# NullAnalyser.net
KiCad netlist of a schematic drawn in EAGLE
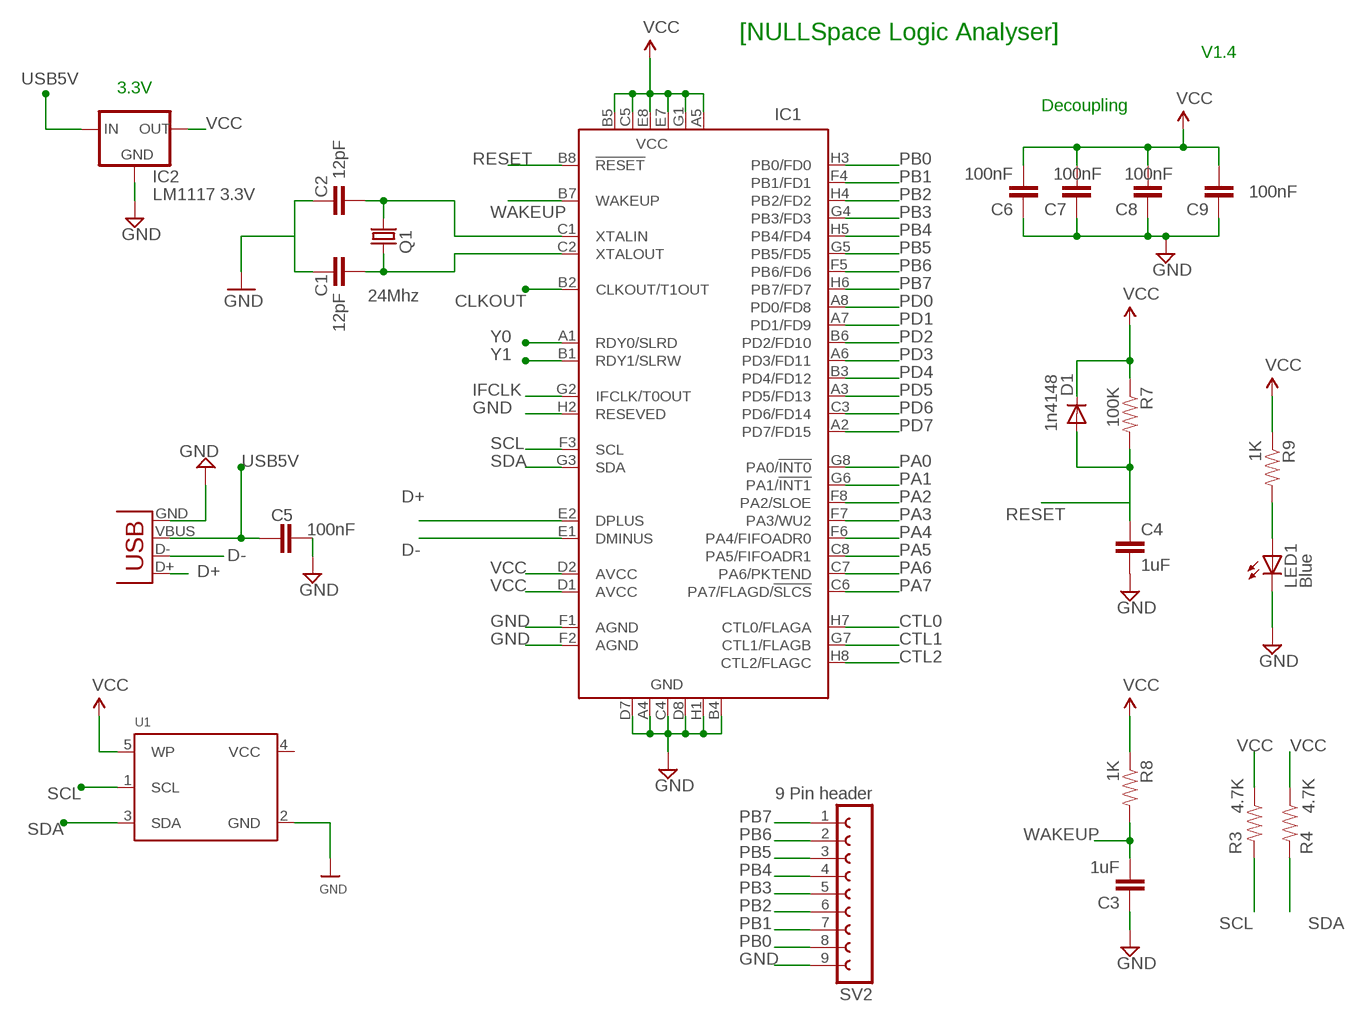
[diagram p0: schematic, sheet 1]

(export (version "E")
  (design (tool "Eeschema 10.0.6"))
  (components
    (comp (ref "C1")
      (value "12pF")
      (footprint "eagle-import:0402-CAP")
      (fields (field (name "MF") "KEMET") (field (name "MPN") "C0805C120J5GACTU"))
      (libsource (lib "eagle-import") (part "CAP0402-CAP"))
    )
    (comp (ref "C2")
      (value "12pF")
      (footprint "eagle-import:0402-CAP")
      (fields (field (name "MF") "KEMET") (field (name "MPN") "C0805C120J5GACTU"))
      (libsource (lib "eagle-import") (part "CAP0402-CAP"))
    )
    (comp (ref "C3")
      (value "1uF")
      (footprint "eagle-import:0402-CAP")
      (fields (field (name "MPN") "C2012Y5V1C105Z/0.85"))
      (libsource (lib "eagle-import") (part "CAP0402-CAP"))
    )
    (comp (ref "C4")
      (value "1uF")
      (footprint "eagle-import:0402-CAP")
      (fields (field (name "MPN") "C2012Y5V1C105Z/0.85"))
      (libsource (lib "eagle-import") (part "CAP0402-CAP"))
    )
    (comp (ref "C5")
      (value "100nF")
      (footprint "eagle-import:0402-CAP")
      (fields (field (name "MF") "FARNELL") (field (name "MPN") "GRM21BR71H104KA01L"))
      (libsource (lib "eagle-import") (part "CAP0402-CAP"))
    )
    (comp (ref "C6")
      (value "100nF")
      (footprint "eagle-import:0402-CAP")
      (fields (field (name "MF") "FARNELL") (field (name "MPN") "GRM21BR71H104KA01L"))
      (libsource (lib "eagle-import") (part "CAP0402-CAP"))
    )
    (comp (ref "C7")
      (value "100nF")
      (footprint "eagle-import:0402-CAP")
      (fields (field (name "MF") "FARNELL") (field (name "MPN") "GRM21BR71H104KA01L"))
      (libsource (lib "eagle-import") (part "CAP0402-CAP"))
    )
    (comp (ref "C8")
      (value "100nF")
      (footprint "eagle-import:0402-CAP")
      (fields (field (name "MF") "FARNELL") (field (name "MPN") "GRM21BR71H104KA01L"))
      (libsource (lib "eagle-import") (part "CAP0402-CAP"))
    )
    (comp (ref "C9")
      (value "100nF")
      (footprint "eagle-import:0402-CAP")
      (fields (field (name "MF") "FARNELL") (field (name "MPN") "GRM21BR71H104KA01L"))
      (libsource (lib "eagle-import") (part "CAP0402-CAP"))
    )
    (comp (ref "D1")
      (value "1n4148")
      (footprint "eagle-import:SOD-323")
      (fields (field (name "MF") "VISHAY/TELEFUNKEN") (field (name "MPN") "1N4148W-V-GS08"))
      (libsource (lib "eagle-import") (part "DIODESOD"))
    )
    (comp (ref "IC1")
      (value "CY7C68014A-56BAXC")
      (footprint "eagle-import:VFBGA56")
      (fields (field (name "MPN") "CY7C68014A-56BAXC") (field (name "OC_NEWARK") "23M5564"))
      (libsource (lib "eagle-import") (part "CY7C6801A-56BAXC4"))
    )
    (comp (ref "IC2")
      (value "LM1117 3.3V")
      (footprint "eagle-import:SOT223")
      (fields (field (name "MF") "NATIONAL SEMICONDUCTOR") (field (name "MPN") "LM1117MPX-3.3"))
      (libsource (lib "eagle-import") (part "LM1117"))
    )
    (comp (ref "LED1")
      (value "Blue")
      (footprint "eagle-import:LED-0603")
      (fields (field (name "MPN") "5988210107F"))
      (libsource (lib "eagle-import") (part "LED0603"))
    )
    (comp (ref "Q1")
      (value "24Mhz")
      (footprint "eagle-import:CRYSTAL-SMD-TWO-PAD")
      (fields (field (name "MF") "Abracon Corporation") (field (name "MPN") "ABM3-24.000MHZ-B2-T"))
      (libsource (lib "eagle-import") (part "CRYSTALTWO-PADTWO-PAD"))
    )
    (comp (ref "R3")
      (value "4.7K")
      (footprint "eagle-import:0402-RES")
      (fields (field (name "MPN") "CRCW08054K70JNEA"))
      (libsource (lib "eagle-import") (part "RESISTOR0402-RES"))
    )
    (comp (ref "R4")
      (value "4.7K")
      (footprint "eagle-import:0402-RES")
      (fields (field (name "MPN") "CRCW08054K70JNEA"))
      (libsource (lib "eagle-import") (part "RESISTOR0402-RES"))
    )
    (comp (ref "R7")
      (value "100K")
      (footprint "eagle-import:0402-RES")
      (fields (field (name "MPN") "MCTF0805DTC1002"))
      (libsource (lib "eagle-import") (part "RESISTOR0402-RES"))
    )
    (comp (ref "R8")
      (value "1K")
      (footprint "eagle-import:0402-RES")
      (fields (field (name "MPN") "MCTF0805DTC1001"))
      (libsource (lib "eagle-import") (part "RESISTOR0402-RES"))
    )
    (comp (ref "R9")
      (value "1K")
      (footprint "eagle-import:0402-RES")
      (fields (field (name "MPN") "MCTF0805DTC1001"))
      (libsource (lib "eagle-import") (part "RESISTOR0402-RES"))
    )
    (comp (ref "SV2")
      (value "9 Pin header")
      (footprint "eagle-import:FE09")
      (fields (field (name "OC_NEWARK") "unknown"))
      (libsource (lib "eagle-import") (part "FE09-1"))
    )
    (comp (ref "U1")
      (value "MCP24AA32")
      (footprint "eagle-import:SOT23-5")
      (fields (field (name "MF") "MICROCHIP") (field (name "MPN") "24LC00T-I/OT"))
      (libsource (lib "eagle-import") (part "MCP24AA32"))
    )
    (comp (ref "X1")
      (value "USB-MICROB")
      (footprint "eagle-import:USB-MICROB")
      (fields (field (name "MPN") "1734035-1"))
      (libsource (lib "eagle-import") (part "USB-MICROB"))
    )
  )
  (nets
    (net (code "1") (name "/CLKOUT") (class "Default")
      (node (ref "IC1") (pin "B2") (pinfunction "CLKOUT/T1OUT_B2") (pintype "input"))
    )
    (net (code "2") (name "/CTL0") (class "Default")
      (node (ref "IC1") (pin "H7") (pinfunction "CTL0/FLAGA_H7") (pintype "output"))
    )
    (net (code "3") (name "/CTL1") (class "Default")
      (node (ref "IC1") (pin "G7") (pinfunction "CTL1/FLAGB_G7") (pintype "output"))
    )
    (net (code "4") (name "/CTL2") (class "Default")
      (node (ref "IC1") (pin "H8") (pinfunction "CTL2/FLAGC_H8") (pintype "output"))
    )
    (net (code "5") (name "/D+") (class "Default")
      (node (ref "IC1") (pin "E2") (pinfunction "DPLUS_E2") (pintype "bidirectional"))
      (node (ref "X1") (pin "D+") (pinfunction "D+_D+") (pintype "bidirectional"))
    )
    (net (code "6") (name "/D-") (class "Default")
      (node (ref "IC1") (pin "E1") (pinfunction "DMINUS_E1") (pintype "bidirectional"))
      (node (ref "X1") (pin "D-") (pinfunction "D-_D-") (pintype "bidirectional"))
    )
    (net (code "7") (name "/IFCLK") (class "Default")
      (node (ref "IC1") (pin "G2") (pinfunction "IFCLK/T0OUT_G2") (pintype "bidirectional"))
    )
    (net (code "8") (name "/PA0") (class "Default")
      (node (ref "IC1") (pin "G8") (pinfunction "PA0/~{INT0}_G8") (pintype "bidirectional"))
    )
    (net (code "9") (name "/PA1") (class "Default")
      (node (ref "IC1") (pin "G6") (pinfunction "PA1/~{INT1}_G6") (pintype "bidirectional"))
    )
    (net (code "10") (name "/PA2") (class "Default")
      (node (ref "IC1") (pin "F8") (pinfunction "PA2/SLOE_F8") (pintype "bidirectional"))
    )
    (net (code "11") (name "/PA3") (class "Default")
      (node (ref "IC1") (pin "F7") (pinfunction "PA3/WU2_F7") (pintype "bidirectional"))
    )
    (net (code "12") (name "/PA4") (class "Default")
      (node (ref "IC1") (pin "F6") (pinfunction "PA4/FIFOADR0_F6") (pintype "bidirectional"))
    )
    (net (code "13") (name "/PA5") (class "Default")
      (node (ref "IC1") (pin "C8") (pinfunction "PA5/FIFOADR1_C8") (pintype "bidirectional"))
    )
    (net (code "14") (name "/PA6") (class "Default")
      (node (ref "IC1") (pin "C7") (pinfunction "PA6/PKTEND_C7") (pintype "bidirectional"))
    )
    (net (code "15") (name "/PA7") (class "Default")
      (node (ref "IC1") (pin "C6") (pinfunction "PA7/FLAGD/~{SLCS}_C6") (pintype "bidirectional"))
    )
    (net (code "16") (name "/PB0") (class "Default")
      (node (ref "IC1") (pin "H3") (pinfunction "PB0/FD0_H3") (pintype "bidirectional"))
      (node (ref "SV2") (pin "8") (pinfunction "8_8") (pintype "passive"))
    )
    (net (code "17") (name "/PB1") (class "Default")
      (node (ref "IC1") (pin "F4") (pinfunction "PB1/FD1_F4") (pintype "bidirectional"))
      (node (ref "SV2") (pin "7") (pinfunction "7_7") (pintype "passive"))
    )
    (net (code "18") (name "/PB2") (class "Default")
      (node (ref "IC1") (pin "H4") (pinfunction "PB2/FD2_H4") (pintype "bidirectional"))
      (node (ref "SV2") (pin "6") (pinfunction "6_6") (pintype "passive"))
    )
    (net (code "19") (name "/PB3") (class "Default")
      (node (ref "IC1") (pin "G4") (pinfunction "PB3/FD3_G4") (pintype "bidirectional"))
      (node (ref "SV2") (pin "5") (pinfunction "5_5") (pintype "passive"))
    )
    (net (code "20") (name "/PB4") (class "Default")
      (node (ref "IC1") (pin "H5") (pinfunction "PB4/FD4_H5") (pintype "bidirectional"))
      (node (ref "SV2") (pin "4") (pinfunction "4_4") (pintype "passive"))
    )
    (net (code "21") (name "/PB5") (class "Default")
      (node (ref "IC1") (pin "G5") (pinfunction "PB5/FD5_G5") (pintype "bidirectional"))
      (node (ref "SV2") (pin "3") (pinfunction "3_3") (pintype "passive"))
    )
    (net (code "22") (name "/PB6") (class "Default")
      (node (ref "IC1") (pin "F5") (pinfunction "PB6/FD6_F5") (pintype "bidirectional"))
      (node (ref "SV2") (pin "2") (pinfunction "2_2") (pintype "passive"))
    )
    (net (code "23") (name "/PB7") (class "Default")
      (node (ref "IC1") (pin "H6") (pinfunction "PB7/FD7_H6") (pintype "bidirectional"))
      (node (ref "SV2") (pin "1") (pinfunction "1_1") (pintype "passive"))
    )
    (net (code "24") (name "/PD0") (class "Default")
      (node (ref "IC1") (pin "A8") (pinfunction "PD0/FD8_A8") (pintype "bidirectional"))
    )
    (net (code "25") (name "/PD1") (class "Default")
      (node (ref "IC1") (pin "A7") (pinfunction "PD1/FD9_A7") (pintype "bidirectional"))
    )
    (net (code "26") (name "/PD2") (class "Default")
      (node (ref "IC1") (pin "B6") (pinfunction "PD2/FD10_B6") (pintype "bidirectional"))
    )
    (net (code "27") (name "/PD3") (class "Default")
      (node (ref "IC1") (pin "A6") (pinfunction "PD3/FD11_A6") (pintype "bidirectional"))
    )
    (net (code "28") (name "/PD4") (class "Default")
      (node (ref "IC1") (pin "B3") (pinfunction "PD4/FD12_B3") (pintype "bidirectional"))
    )
    (net (code "29") (name "/PD5") (class "Default")
      (node (ref "IC1") (pin "A3") (pinfunction "PD5/FD13_A3") (pintype "bidirectional"))
    )
    (net (code "30") (name "/PD6") (class "Default")
      (node (ref "IC1") (pin "C3") (pinfunction "PD6/FD14_C3") (pintype "bidirectional"))
    )
    (net (code "31") (name "/PD7") (class "Default")
      (node (ref "IC1") (pin "A2") (pinfunction "PD7/FD15_A2") (pintype "bidirectional"))
    )
    (net (code "32") (name "/RESET") (class "Default")
      (node (ref "C4") (pin "1") (pinfunction "1_1") (pintype "passive"))
      (node (ref "D1") (pin "2") (pinfunction "A_2") (pintype "passive"))
      (node (ref "IC1") (pin "B8") (pinfunction "~{RESET}_B8") (pintype "input"))
      (node (ref "R7") (pin "2") (pinfunction "2_2") (pintype "passive"))
    )
    (net (code "33") (name "/SCL") (class "Default")
      (node (ref "IC1") (pin "F3") (pinfunction "SCL_F3") (pintype "output"))
      (node (ref "R3") (pin "2") (pinfunction "2_2") (pintype "passive"))
      (node (ref "U1") (pin "1") (pinfunction "SCL_1") (pintype "bidirectional"))
    )
    (net (code "34") (name "/SDA") (class "Default")
      (node (ref "IC1") (pin "G3") (pinfunction "SDA_G3") (pintype "bidirectional"))
      (node (ref "R4") (pin "2") (pinfunction "2_2") (pintype "passive"))
      (node (ref "U1") (pin "3") (pinfunction "SDA_3") (pintype "bidirectional"))
    )
    (net (code "35") (name "/USB5V") (class "Default")
      (node (ref "C5") (pin "1") (pinfunction "1_1") (pintype "passive"))
      (node (ref "IC2") (pin "3") (pinfunction "IN_3") (pintype "input"))
      (node (ref "X1") (pin "VBUS") (pinfunction "VBUS_VBUS") (pintype "bidirectional"))
    )
    (net (code "36") (name "/WAKEUP") (class "Default")
      (node (ref "C3") (pin "2") (pinfunction "2_2") (pintype "passive"))
      (node (ref "IC1") (pin "B7") (pinfunction "WAKEUP_B7") (pintype "input"))
      (node (ref "R8") (pin "2") (pinfunction "2_2") (pintype "passive"))
    )
    (net (code "37") (name "/Y0") (class "Default")
      (node (ref "IC1") (pin "A1") (pinfunction "RDY0/SLRD_A1") (pintype "input"))
    )
    (net (code "38") (name "/Y1") (class "Default")
      (node (ref "IC1") (pin "B1") (pinfunction "RDY1/SLRW_B1") (pintype "input"))
    )
    (net (code "39") (name "GND") (class "Default")
      (node (ref "C1") (pin "1") (pinfunction "1_1") (pintype "passive"))
      (node (ref "C2") (pin "2") (pinfunction "2_2") (pintype "passive"))
      (node (ref "C3") (pin "1") (pinfunction "1_1") (pintype "passive"))
      (node (ref "C4") (pin "2") (pinfunction "2_2") (pintype "passive"))
      (node (ref "C5") (pin "2") (pinfunction "2_2") (pintype "passive"))
      (node (ref "C6") (pin "1") (pinfunction "1_1") (pintype "passive"))
      (node (ref "C7") (pin "1") (pinfunction "1_1") (pintype "passive"))
      (node (ref "C8") (pin "1") (pinfunction "1_1") (pintype "passive"))
      (node (ref "C9") (pin "1") (pinfunction "1_1") (pintype "passive"))
      (node (ref "IC1") (pin "A4") (pinfunction "GND_A4") (pintype "input"))
      (node (ref "IC1") (pin "B4") (pinfunction "GND_B4") (pintype "input"))
      (node (ref "IC1") (pin "C4") (pinfunction "GND_C4") (pintype "input"))
      (node (ref "IC1") (pin "D7") (pinfunction "GND_D7") (pintype "input"))
      (node (ref "IC1") (pin "D8") (pinfunction "GND_D8") (pintype "input"))
      (node (ref "IC1") (pin "F1") (pinfunction "AGND_F1") (pintype "input"))
      (node (ref "IC1") (pin "F2") (pinfunction "AGND_F2") (pintype "input"))
      (node (ref "IC1") (pin "H1") (pinfunction "GND_H1") (pintype "input"))
      (node (ref "IC1") (pin "H2") (pinfunction "RESEVED_H2") (pintype "input"))
      (node (ref "IC2") (pin "1") (pinfunction "GND_1") (pintype "input"))
      (node (ref "LED1") (pin "C") (pinfunction "C_C") (pintype "passive"))
      (node (ref "SV2") (pin "9") (pinfunction "9_9") (pintype "passive"))
      (node (ref "U1") (pin "2") (pinfunction "GND_2") (pintype "bidirectional"))
      (node (ref "X1") (pin "GND") (pinfunction "GND_GND") (pintype "bidirectional"))
    )
    (net (code "40") (name "Net-(IC1-XTALIN)") (class "Default")
      (node (ref "C2") (pin "1") (pinfunction "1_1") (pintype "passive"))
      (node (ref "IC1") (pin "C1") (pinfunction "XTALIN_C1") (pintype "input"))
      (node (ref "Q1") (pin "2") (pinfunction "2_2") (pintype "passive"))
    )
    (net (code "41") (name "Net-(IC1-XTALOUT)") (class "Default")
      (node (ref "C1") (pin "2") (pinfunction "2_2") (pintype "passive"))
      (node (ref "IC1") (pin "C2") (pinfunction "XTALOUT_C2") (pintype "input"))
      (node (ref "Q1") (pin "1") (pinfunction "1_1") (pintype "passive"))
    )
    (net (code "42") (name "Net-(LED1-PadA)") (class "Default")
      (node (ref "LED1") (pin "A") (pinfunction "A_A") (pintype "passive"))
      (node (ref "R9") (pin "2") (pinfunction "2_2") (pintype "passive"))
    )
    (net (code "43") (name "VCC") (class "Default")
      (node (ref "C6") (pin "2") (pinfunction "2_2") (pintype "passive"))
      (node (ref "C7") (pin "2") (pinfunction "2_2") (pintype "passive"))
      (node (ref "C8") (pin "2") (pinfunction "2_2") (pintype "passive"))
      (node (ref "C9") (pin "2") (pinfunction "2_2") (pintype "passive"))
      (node (ref "D1") (pin "1") (pinfunction "C_1") (pintype "passive"))
      (node (ref "IC1") (pin "A5") (pinfunction "VCC_A5") (pintype "input"))
      (node (ref "IC1") (pin "B5") (pinfunction "VCC_B5") (pintype "input"))
      (node (ref "IC1") (pin "C5") (pinfunction "VCC_C5") (pintype "input"))
      (node (ref "IC1") (pin "D1") (pinfunction "AVCC_D1") (pintype "input"))
      (node (ref "IC1") (pin "D2") (pinfunction "AVCC_D2") (pintype "input"))
      (node (ref "IC1") (pin "E7") (pinfunction "VCC_E7") (pintype "input"))
      (node (ref "IC1") (pin "E8") (pinfunction "VCC_E8") (pintype "input"))
      (node (ref "IC1") (pin "G1") (pinfunction "VCC_G1") (pintype "input"))
      (node (ref "IC2") (pin "2") (pinfunction "OUT_2") (pintype "passive"))
      (node (ref "R3") (pin "1") (pinfunction "1_1") (pintype "passive"))
      (node (ref "R4") (pin "1") (pinfunction "1_1") (pintype "passive"))
      (node (ref "R7") (pin "1") (pinfunction "1_1") (pintype "passive"))
      (node (ref "R8") (pin "1") (pinfunction "1_1") (pintype "passive"))
      (node (ref "R9") (pin "1") (pinfunction "1_1") (pintype "passive"))
      (node (ref "U1") (pin "5") (pinfunction "WP_5") (pintype "bidirectional"))
    )
    (net (code "44") (name "unconnected-(U1-VCC-Pad4)") (class "Default")
      (node (ref "U1") (pin "4") (pinfunction "VCC_4") (pintype "bidirectional"))
    )
  )
)
